# buttons.net
KiCad netlist of a schematic drawn in EAGLE
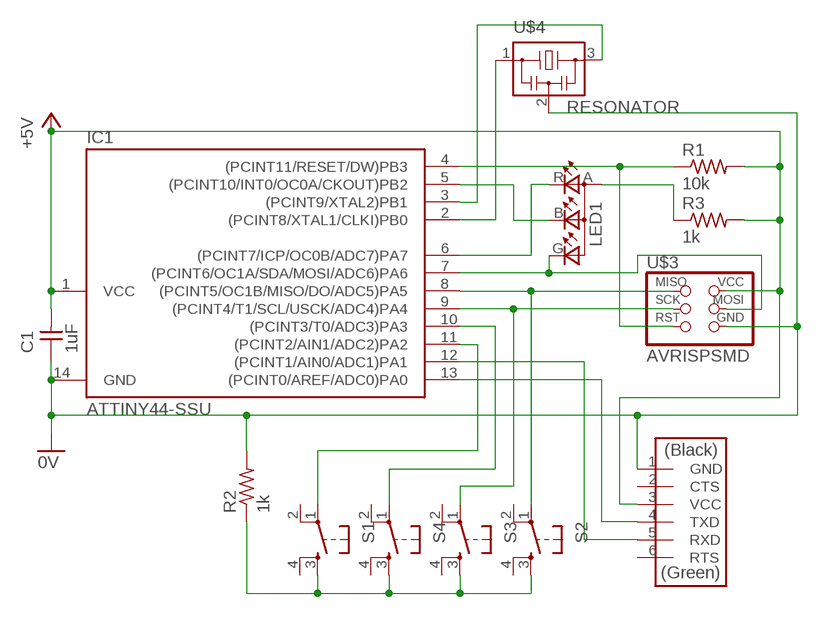
[diagram p0: schematic, sheet 1]

(export (version "E")
  (design (tool "Eeschema 10.0.6"))
  (components
    (comp (ref "C1")
      (value "1uF")
      (footprint "eagle-import:C1206FAB")
      (libsource (lib "eagle-import") (part "CAP-UNPOLARIZEDFAB"))
    )
    (comp (ref "IC1")
      (value "ATTINY44-SSU")
      (footprint "eagle-import:SOIC14")
      (libsource (lib "eagle-import") (part "ATTINY44-SSU"))
    )
    (comp (ref "LED1")
      (value "LEDRGBOLD")
      (footprint "eagle-import:P-LCC-4-3")
      (libsource (lib "eagle-import") (part "LEDRGBOLD"))
    )
    (comp (ref "R1")
      (value "10k")
      (footprint "eagle-import:R1206FAB")
      (libsource (lib "eagle-import") (part "RES-US1206FAB"))
    )
    (comp (ref "R2")
      (value "1k")
      (footprint "eagle-import:R1206FAB")
      (libsource (lib "eagle-import") (part "RES-US1206FAB"))
    )
    (comp (ref "R3")
      (value "1k")
      (footprint "eagle-import:R1206FAB")
      (libsource (lib "eagle-import") (part "RES-US1206FAB"))
    )
    (comp (ref "S1")
      (value "6MM_SWITCH6MM_SWITCH")
      (footprint "eagle-import:6MM_SWITCH")
      (libsource (lib "eagle-import") (part "6MM_SWITCH6MM_SWITCH"))
    )
    (comp (ref "S2")
      (value "6MM_SWITCH6MM_SWITCH")
      (footprint "eagle-import:6MM_SWITCH")
      (libsource (lib "eagle-import") (part "6MM_SWITCH6MM_SWITCH"))
    )
    (comp (ref "S3")
      (value "6MM_SWITCH6MM_SWITCH")
      (footprint "eagle-import:6MM_SWITCH")
      (libsource (lib "eagle-import") (part "6MM_SWITCH6MM_SWITCH"))
    )
    (comp (ref "S4")
      (value "6MM_SWITCH6MM_SWITCH")
      (footprint "eagle-import:6MM_SWITCH")
      (libsource (lib "eagle-import") (part "6MM_SWITCH6MM_SWITCH"))
    )
    (comp (ref "U$2")
      (value "FTDI-SMD-HEADER")
      (footprint "eagle-import:1X06SMD")
      (libsource (lib "eagle-import") (part "FTDI-SMD-HEADER"))
    )
    (comp (ref "U$3")
      (value "AVRISPSMD")
      (footprint "eagle-import:2X03SMD")
      (libsource (lib "eagle-import") (part "AVRISPSMD"))
    )
    (comp (ref "U$4")
      (value "RESONATOR")
      (footprint "eagle-import:EFOBM")
      (libsource (lib "eagle-import") (part "RESONATOR"))
    )
  )
  (nets
    (net (code "1") (name "+5V") (class "Default")
      (node (ref "C1") (pin "2") (pinfunction "2_2") (pintype "passive"))
      (node (ref "IC1") (pin "1") (pinfunction "VCC_1") (pintype "power_in"))
      (node (ref "R1") (pin "2") (pinfunction "2_2") (pintype "passive"))
      (node (ref "R3") (pin "2") (pinfunction "2_2") (pintype "passive"))
      (node (ref "U$2") (pin "3") (pinfunction "VCC_3") (pintype "bidirectional"))
      (node (ref "U$3") (pin "2") (pinfunction "VCC_2") (pintype "passive"))
    )
    (net (code "2") (name "0V") (class "Default")
      (node (ref "C1") (pin "1") (pinfunction "1_1") (pintype "passive"))
      (node (ref "IC1") (pin "14") (pinfunction "GND_14") (pintype "power_in"))
      (node (ref "R2") (pin "2") (pinfunction "2_2") (pintype "passive"))
      (node (ref "U$2") (pin "1") (pinfunction "GND_1") (pintype "bidirectional"))
      (node (ref "U$3") (pin "6") (pinfunction "GND_6") (pintype "passive"))
      (node (ref "U$4") (pin "2") (pinfunction "2_2") (pintype "passive"))
    )
    (net (code "3") (name "Net-(IC1-(PCINT0{slash}AREF{slash}ADC0)PA0)") (class "Default")
      (node (ref "IC1") (pin "13") (pinfunction "(PCINT0/AREF/ADC0)PA0_13") (pintype "bidirectional"))
      (node (ref "U$2") (pin "4") (pinfunction "TXD_4") (pintype "bidirectional"))
    )
    (net (code "4") (name "Net-(IC1-(PCINT1{slash}AIN0{slash}ADC1)PA1)") (class "Default")
      (node (ref "IC1") (pin "12") (pinfunction "(PCINT1/AIN0/ADC1)PA1_12") (pintype "bidirectional"))
      (node (ref "U$2") (pin "5") (pinfunction "RXD_5") (pintype "bidirectional"))
    )
    (net (code "5") (name "Net-(IC1-(PCINT2{slash}AIN1{slash}ADC2)PA2)") (class "Default")
      (node (ref "IC1") (pin "11") (pinfunction "(PCINT2/AIN1/ADC2)PA2_11") (pintype "bidirectional"))
      (node (ref "S1") (pin "1") (pinfunction "P_1") (pintype "passive"))
    )
    (net (code "6") (name "Net-(IC1-(PCINT3{slash}T0{slash}ADC3)PA3)") (class "Default")
      (node (ref "IC1") (pin "10") (pinfunction "(PCINT3/T0/ADC3)PA3_10") (pintype "bidirectional"))
      (node (ref "S4") (pin "1") (pinfunction "P_1") (pintype "passive"))
    )
    (net (code "7") (name "Net-(IC1-(PCINT4{slash}T1{slash}SCL{slash}USCK{slash}ADC4)PA4)") (class "Default")
      (node (ref "IC1") (pin "9") (pinfunction "(PCINT4/T1/SCL/USCK/ADC4)PA4_9") (pintype "bidirectional"))
      (node (ref "S3") (pin "1") (pinfunction "P_1") (pintype "passive"))
      (node (ref "U$3") (pin "3") (pinfunction "SCK_3") (pintype "passive"))
    )
    (net (code "8") (name "Net-(IC1-(PCINT5{slash}OC1B{slash}MISO{slash}DO{slash}ADC5)PA5)") (class "Default")
      (node (ref "IC1") (pin "8") (pinfunction "(PCINT5/OC1B/MISO/DO/ADC5)PA5_8") (pintype "bidirectional"))
      (node (ref "S2") (pin "1") (pinfunction "P_1") (pintype "passive"))
      (node (ref "U$3") (pin "1") (pinfunction "MISO_1") (pintype "passive"))
    )
    (net (code "9") (name "Net-(IC1-(PCINT6{slash}OC1A{slash}SDA{slash}MOSI{slash}ADC6)PA6)") (class "Default")
      (node (ref "IC1") (pin "7") (pinfunction "(PCINT6/OC1A/SDA/MOSI/ADC6)PA6_7") (pintype "bidirectional"))
      (node (ref "LED1") (pin "G") (pinfunction "CGREEN_G") (pintype "passive"))
      (node (ref "U$3") (pin "4") (pinfunction "MOSI_4") (pintype "passive"))
    )
    (net (code "10") (name "Net-(IC1-(PCINT7{slash}ICP{slash}OC0B{slash}ADC7)PA7)") (class "Default")
      (node (ref "IC1") (pin "6") (pinfunction "(PCINT7/ICP/OC0B/ADC7)PA7_6") (pintype "bidirectional"))
      (node (ref "LED1") (pin "R") (pinfunction "CRED_R") (pintype "passive"))
    )
    (net (code "11") (name "Net-(IC1-(PCINT8{slash}XTAL1{slash}CLKI)PB0)") (class "Default")
      (node (ref "IC1") (pin "2") (pinfunction "(PCINT8/XTAL1/CLKI)PB0_2") (pintype "bidirectional"))
      (node (ref "U$4") (pin "1") (pinfunction "1_1") (pintype "passive"))
    )
    (net (code "12") (name "Net-(IC1-(PCINT9{slash}XTAL2)PB1)") (class "Default")
      (node (ref "IC1") (pin "3") (pinfunction "(PCINT9/XTAL2)PB1_3") (pintype "bidirectional"))
      (node (ref "U$4") (pin "3") (pinfunction "3_3") (pintype "passive"))
    )
    (net (code "13") (name "Net-(IC1-(PCINT10{slash}INT0{slash}OC0A{slash}CKOUT)PB2)") (class "Default")
      (node (ref "IC1") (pin "5") (pinfunction "(PCINT10/INT0/OC0A/CKOUT)PB2_5") (pintype "bidirectional"))
      (node (ref "LED1") (pin "B") (pinfunction "CBLUE_B") (pintype "passive"))
    )
    (net (code "14") (name "Net-(IC1-(PCINT11{slash}RESET{slash}DW)PB3)") (class "Default")
      (node (ref "IC1") (pin "4") (pinfunction "(PCINT11/RESET/DW)PB3_4") (pintype "bidirectional"))
      (node (ref "R1") (pin "1") (pinfunction "1_1") (pintype "passive"))
      (node (ref "U$3") (pin "5") (pinfunction "RST_5") (pintype "passive"))
    )
    (net (code "15") (name "Net-(LED1-A2)") (class "Default")
      (node (ref "LED1") (pin "A") (pinfunction "A2_A") (pintype "passive"))
      (node (ref "R3") (pin "1") (pinfunction "1_1") (pintype "passive"))
    )
    (net (code "16") (name "Net-(S1-S)") (class "Default")
      (node (ref "R2") (pin "1") (pinfunction "1_1") (pintype "passive"))
      (node (ref "S1") (pin "3") (pinfunction "S_3") (pintype "passive"))
      (node (ref "S2") (pin "3") (pinfunction "S_3") (pintype "passive"))
      (node (ref "S3") (pin "3") (pinfunction "S_3") (pintype "passive"))
      (node (ref "S4") (pin "3") (pinfunction "S_3") (pintype "passive"))
    )
    (net (code "17") (name "unconnected-(S1-P1-Pad2)") (class "Default")
      (node (ref "S1") (pin "2") (pinfunction "P1_2") (pintype "passive"))
    )
    (net (code "18") (name "unconnected-(S1-S1-Pad4)") (class "Default")
      (node (ref "S1") (pin "4") (pinfunction "S1_4") (pintype "passive"))
    )
    (net (code "19") (name "unconnected-(S2-P1-Pad2)") (class "Default")
      (node (ref "S2") (pin "2") (pinfunction "P1_2") (pintype "passive"))
    )
    (net (code "20") (name "unconnected-(S2-S1-Pad4)") (class "Default")
      (node (ref "S2") (pin "4") (pinfunction "S1_4") (pintype "passive"))
    )
    (net (code "21") (name "unconnected-(S3-P1-Pad2)") (class "Default")
      (node (ref "S3") (pin "2") (pinfunction "P1_2") (pintype "passive"))
    )
    (net (code "22") (name "unconnected-(S3-S1-Pad4)") (class "Default")
      (node (ref "S3") (pin "4") (pinfunction "S1_4") (pintype "passive"))
    )
    (net (code "23") (name "unconnected-(S4-P1-Pad2)") (class "Default")
      (node (ref "S4") (pin "2") (pinfunction "P1_2") (pintype "passive"))
    )
    (net (code "24") (name "unconnected-(S4-S1-Pad4)") (class "Default")
      (node (ref "S4") (pin "4") (pinfunction "S1_4") (pintype "passive"))
    )
    (net (code "25") (name "unconnected-(U$2-CTS-Pad2)") (class "Default")
      (node (ref "U$2") (pin "2") (pinfunction "CTS_2") (pintype "bidirectional"))
    )
    (net (code "26") (name "unconnected-(U$2-RTS-Pad6)") (class "Default")
      (node (ref "U$2") (pin "6") (pinfunction "RTS_6") (pintype "bidirectional"))
    )
  )
)
